# Lighting.net
KiCad netlist of a schematic drawn in Altium Designer
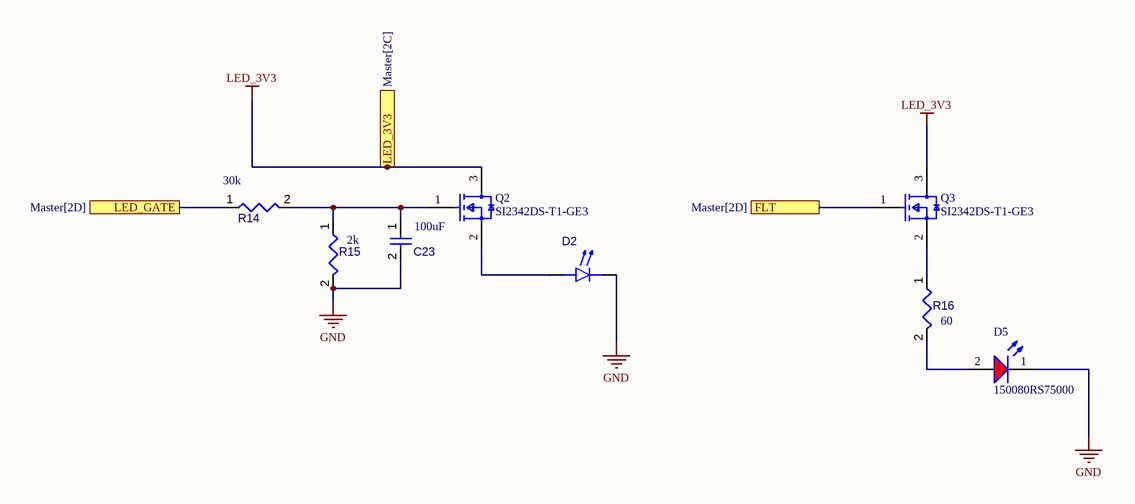
[diagram p0: Lighting.SchDoc]

(export (version "E")
  (design (tool "Eeschema 10.0.6"))
  (components
    (comp (ref "C23")
      (value "100uF")
      (description "Capacitor")
      (fields (field (name "Comment") "Capacitors,100uF"))
      (libsource (lib "Brian Tan") (part "CAP-NP-2"))
    )
    (comp (ref "D2")
      (value "HL-AM-2835H489W-S1-08HL-HR3")
      (footprint "HL-AM-2835H489W-S1-08HL-HR3-Footprint-1")
      (libsource (lib "Brian Tan") (part "DIODE-LED-2"))
    )
    (comp (ref "D5")
      (value "150080RS75000")
      (footprint "WL-SMCW_0805_150080xx75000")
      (description "LED Uni-Color Red 630nm 2-Pin Chip 0805(2012Metric) T/R")
      (libsource (lib "Altium Content Vault") (part "LED_Red_2A-1K"))
    )
    (comp (ref "Q2")
      (value "SI2342DS-T1-GE3")
      (footprint "FP-S-03946-MFG")
      (description "MOSFET N-CH 8V 6A SOT-23")
      (fields
        (field (name "OCTOPART") "https://octopart.com/si2342ds-t1-ge3-vishay-45050957")
        (field (name "MANUFACTURER") "Vishay")
      )
      (libsource (lib "Altium Content Vault") (part "1661867509f36a4ffa577829538a895"))
    )
    (comp (ref "Q3")
      (value "SI2342DS-T1-GE3")
      (footprint "FP-S-03946-MFG")
      (description "MOSFET N-CH 8V 6A SOT-23")
      (fields
        (field (name "OCTOPART") "https://octopart.com/si2342ds-t1-ge3-vishay-45050957")
        (field (name "MANUFACTURER") "Vishay")
      )
      (libsource (lib "Altium Content Vault") (part "1661867509f36a4ffa577829538a895"))
    )
    (comp (ref "R14")
      (value "30k")
      (description "Resistor")
      (fields (field (name "Comment") "Resistors,30k"))
      (libsource (lib "Brian Tan") (part "RES-2"))
    )
    (comp (ref "R15")
      (value "2k")
      (description "Resistor")
      (fields (field (name "Comment") "Resistors,2k"))
      (libsource (lib "Brian Tan") (part "RES-2"))
    )
    (comp (ref "R16")
      (value "60")
      (description "Resistor")
      (fields (field (name "Comment") "Resistors,60"))
      (libsource (lib "Brian Tan") (part "RES-2"))
    )
  )
  (nets
    (net (code "1") (name "/FLT") (class "Default")
      (node (ref "Q3") (pin "1") (pinfunction "G_1") (pintype "passive"))
    )
    (net (code "2") (name "/LED_GATE") (class "Default")
      (node (ref "R14") (pin "1") (pinfunction "1_1") (pintype "passive"))
    )
    (net (code "3") (name "GND") (class "Default")
      (node (ref "C23") (pin "2") (pinfunction "2_2") (pintype "passive"))
      (node (ref "D2") (pin "1") (pinfunction "K_1") (pintype "passive"))
      (node (ref "D5") (pin "1") (pinfunction "K_1") (pintype "passive"))
      (node (ref "R15") (pin "2") (pinfunction "2_2") (pintype "passive"))
    )
    (net (code "4") (name "LED_3V3") (class "Default")
      (node (ref "Q2") (pin "3") (pinfunction "D_3") (pintype "passive"))
      (node (ref "Q3") (pin "3") (pinfunction "D_3") (pintype "passive"))
    )
    (net (code "5") (name "Net-(D2-A)") (class "Default")
      (node (ref "D2") (pin "2") (pinfunction "A_2") (pintype "passive"))
      (node (ref "Q2") (pin "2") (pinfunction "S_2") (pintype "passive"))
    )
    (net (code "6") (name "Net-(D5-A)") (class "Default")
      (node (ref "D5") (pin "2") (pinfunction "A_2") (pintype "passive"))
      (node (ref "R16") (pin "2") (pinfunction "2_2") (pintype "passive"))
    )
    (net (code "7") (name "Net-(Q2-G)") (class "Default")
      (node (ref "C23") (pin "1") (pinfunction "1_1") (pintype "passive"))
      (node (ref "Q2") (pin "1") (pinfunction "G_1") (pintype "passive"))
      (node (ref "R14") (pin "2") (pinfunction "2_2") (pintype "passive"))
      (node (ref "R15") (pin "1") (pinfunction "1_1") (pintype "passive"))
    )
    (net (code "8") (name "Net-(Q3-S)") (class "Default")
      (node (ref "Q3") (pin "2") (pinfunction "S_2") (pintype "passive"))
      (node (ref "R16") (pin "1") (pinfunction "1_1") (pintype "passive"))
    )
  )
)
